# PuzzleTemperatureHumidiy_v1_0.net
KiCad netlist of a schematic drawn in EAGLE
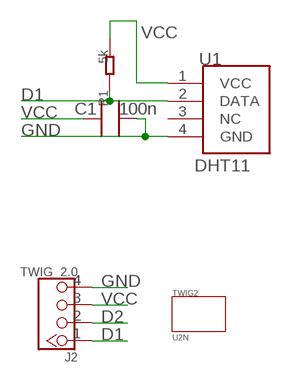
[diagram p0: schematic, sheet 1]

(export (version "E")
  (design (tool "Eeschema 10.0.6"))
  (components
    (comp (ref "C1")
      (value "100n")
      (footprint "eagle-import:0603")
      (libsource (lib "eagle-import") (part "C0603"))
    )
    (comp (ref "J2")
      (value "TWIG_2.0")
      (footprint "eagle-import:2.0_1X4")
      (libsource (lib "eagle-import") (part "TWIG_2.0"))
    )
    (comp (ref "R1")
      (value "5k")
      (footprint "eagle-import:0603")
      (libsource (lib "eagle-import") (part "R0603"))
    )
    (comp (ref "TWIG2")
      (value "U2N")
      (footprint "eagle-import:U2N")
      (libsource (lib "eagle-import") (part "U2N"))
    )
    (comp (ref "U1")
      (value "DHT11")
      (footprint "eagle-import:DHT11")
      (libsource (lib "eagle-import") (part "DHT11"))
    )
  )
  (nets
    (net (code "1") (name "/D1") (class "Default")
      (node (ref "J2") (pin "1") (pinfunction "1_1") (pintype "bidirectional"))
      (node (ref "R1") (pin "1") (pinfunction "1_1") (pintype "bidirectional"))
      (node (ref "U1") (pin "2") (pinfunction "DATA_2") (pintype "bidirectional"))
    )
    (net (code "2") (name "/D2") (class "Default")
      (node (ref "J2") (pin "2") (pinfunction "2_2") (pintype "bidirectional"))
    )
    (net (code "3") (name "/GND") (class "Default")
      (node (ref "C1") (pin "2") (pinfunction "2_2") (pintype "bidirectional"))
      (node (ref "J2") (pin "4") (pinfunction "4_4") (pintype "bidirectional"))
      (node (ref "U1") (pin "4") (pinfunction "GND_4") (pintype "bidirectional"))
    )
    (net (code "4") (name "/VCC") (class "Default")
      (node (ref "C1") (pin "1") (pinfunction "1_1") (pintype "bidirectional"))
      (node (ref "J2") (pin "3") (pinfunction "3_3") (pintype "bidirectional"))
      (node (ref "R1") (pin "2") (pinfunction "2_2") (pintype "bidirectional"))
      (node (ref "U1") (pin "1") (pinfunction "VCC_1") (pintype "bidirectional"))
    )
    (net (code "5") (name "unconnected-(U1-NC-Pad3)") (class "Default")
      (node (ref "U1") (pin "3") (pinfunction "NC_3") (pintype "bidirectional"))
    )
  )
)
